# design.net
KiCad netlist of a schematic drawn in Altium Designer
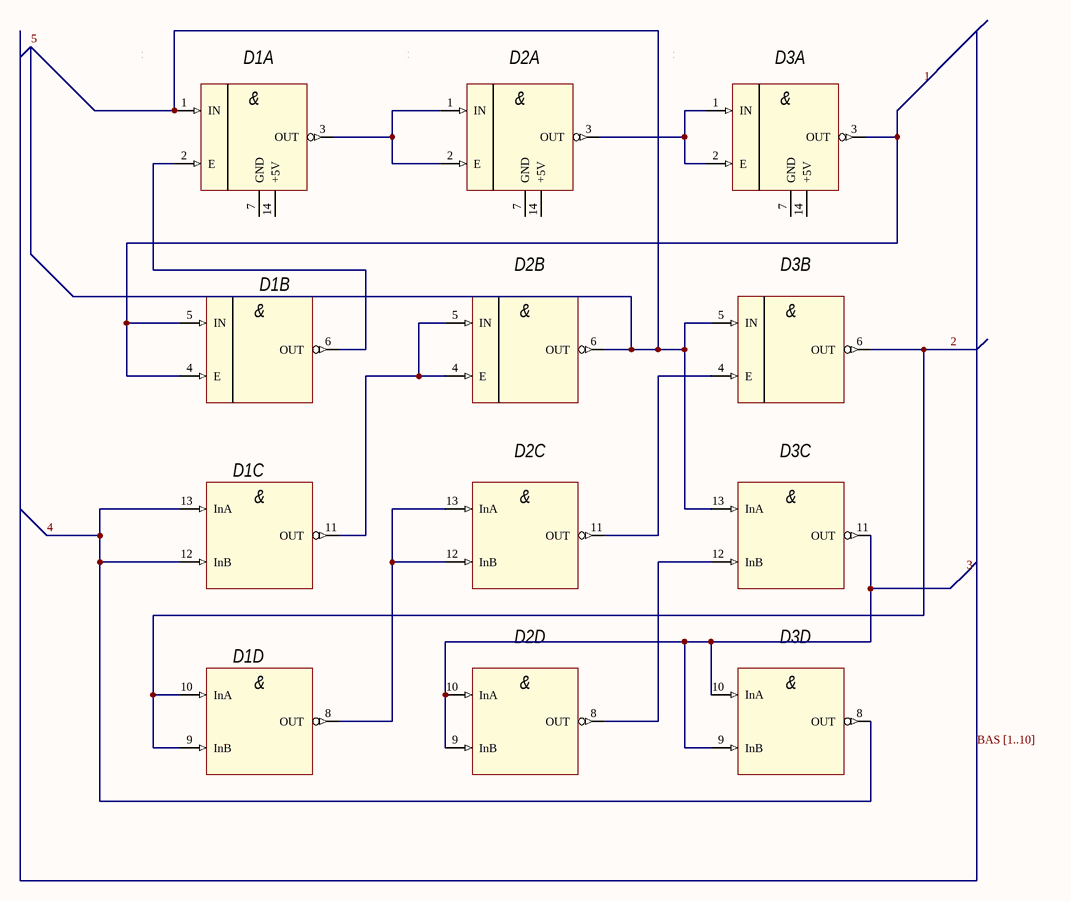
[diagram p0: Принципиальная электрическая схема.SchDoc]

(export (version "E")
  (design (tool "Eeschema 10.0.6"))
  (components
    (comp (ref "D1") (value "НЕ-И") (footprint "DIP14") (libsource (lib "Библиотека УГО") (part "НЕ-И")))
    (comp (ref "D2") (value "НЕ-И") (footprint "DIP14") (libsource (lib "Библиотека УГО") (part "НЕ-И")))
    (comp (ref "D3") (value "НЕ-И") (footprint "DIP14") (libsource (lib "Библиотека УГО") (part "НЕ-И")))
  )
  (nets
    (net (code "1") (name "/1") (class "Default")
      (node (ref "D1") (pin "4") (pinfunction "E_4") (pintype "input"))
      (node (ref "D1") (pin "5") (pinfunction "IN_5") (pintype "input"))
      (node (ref "D3") (pin "3") (pinfunction "OUT_3") (pintype "output"))
    )
    (net (code "2") (name "/2") (class "Default")
      (node (ref "D1") (pin "10") (pinfunction "InA_10") (pintype "input"))
      (node (ref "D1") (pin "9") (pinfunction "InB_9") (pintype "input"))
      (node (ref "D3") (pin "6") (pinfunction "OUT_6") (pintype "output"))
    )
    (net (code "3") (name "/3") (class "Default")
      (node (ref "D2") (pin "10") (pinfunction "InA_10") (pintype "input"))
      (node (ref "D2") (pin "9") (pinfunction "InB_9") (pintype "input"))
      (node (ref "D3") (pin "10") (pinfunction "InA_10") (pintype "input"))
      (node (ref "D3") (pin "11") (pinfunction "OUT_11") (pintype "output"))
      (node (ref "D3") (pin "9") (pinfunction "InB_9") (pintype "input"))
    )
    (net (code "4") (name "/4") (class "Default")
      (node (ref "D1") (pin "12") (pinfunction "InB_12") (pintype "input"))
      (node (ref "D1") (pin "13") (pinfunction "InA_13") (pintype "input"))
      (node (ref "D3") (pin "8") (pinfunction "OUT_8") (pintype "output"))
    )
    (net (code "5") (name "/5") (class "Default")
      (node (ref "D1") (pin "1") (pinfunction "IN_1") (pintype "input"))
      (node (ref "D2") (pin "6") (pinfunction "OUT_6") (pintype "output"))
      (node (ref "D3") (pin "13") (pinfunction "InA_13") (pintype "input"))
      (node (ref "D3") (pin "5") (pinfunction "IN_5") (pintype "input"))
    )
    (net (code "7") (name "Net-(D1A-E)") (class "Default")
      (node (ref "D1") (pin "2") (pinfunction "E_2") (pintype "input"))
      (node (ref "D1") (pin "6") (pinfunction "OUT_6") (pintype "output"))
    )
    (net (code "8") (name "Net-(D1A-OUT)") (class "Default")
      (node (ref "D1") (pin "3") (pinfunction "OUT_3") (pintype "output"))
      (node (ref "D2") (pin "1") (pinfunction "IN_1") (pintype "input"))
      (node (ref "D2") (pin "2") (pinfunction "E_2") (pintype "input"))
    )
    (net (code "9") (name "Net-(D1C-OUT)") (class "Default")
      (node (ref "D1") (pin "11") (pinfunction "OUT_11") (pintype "output"))
      (node (ref "D2") (pin "4") (pinfunction "E_4") (pintype "input"))
      (node (ref "D2") (pin "5") (pinfunction "IN_5") (pintype "input"))
    )
    (net (code "10") (name "Net-(D1D-OUT)") (class "Default")
      (node (ref "D1") (pin "8") (pinfunction "OUT_8") (pintype "output"))
      (node (ref "D2") (pin "12") (pinfunction "InB_12") (pintype "input"))
      (node (ref "D2") (pin "13") (pinfunction "InA_13") (pintype "input"))
    )
    (net (code "11") (name "Net-(D2A-OUT)") (class "Default")
      (node (ref "D2") (pin "3") (pinfunction "OUT_3") (pintype "output"))
      (node (ref "D3") (pin "1") (pinfunction "IN_1") (pintype "input"))
      (node (ref "D3") (pin "2") (pinfunction "E_2") (pintype "input"))
    )
    (net (code "12") (name "Net-(D2C-OUT)") (class "Default")
      (node (ref "D2") (pin "11") (pinfunction "OUT_11") (pintype "output"))
      (node (ref "D3") (pin "4") (pinfunction "E_4") (pintype "input"))
    )
    (net (code "13") (name "Net-(D2D-OUT)") (class "Default")
      (node (ref "D2") (pin "8") (pinfunction "OUT_8") (pintype "output"))
      (node (ref "D3") (pin "12") (pinfunction "InB_12") (pintype "input"))
    )
    (net (code "14") (name "unconnected-(D1A-+5V-Pad14)") (class "Default")
      (node (ref "D1") (pin "14") (pinfunction "+5V_14") (pintype "power_in"))
    )
    (net (code "15") (name "unconnected-(D1A-GND-Pad7)") (class "Default")
      (node (ref "D1") (pin "7") (pinfunction "GND_7") (pintype "power_in"))
    )
    (net (code "16") (name "unconnected-(D2A-+5V-Pad14)") (class "Default")
      (node (ref "D2") (pin "14") (pinfunction "+5V_14") (pintype "power_in"))
    )
    (net (code "17") (name "unconnected-(D2A-GND-Pad7)") (class "Default")
      (node (ref "D2") (pin "7") (pinfunction "GND_7") (pintype "power_in"))
    )
    (net (code "18") (name "unconnected-(D3A-+5V-Pad14)") (class "Default")
      (node (ref "D3") (pin "14") (pinfunction "+5V_14") (pintype "power_in"))
    )
    (net (code "19") (name "unconnected-(D3A-GND-Pad7)") (class "Default")
      (node (ref "D3") (pin "7") (pinfunction "GND_7") (pintype "power_in"))
    )
  )
)
